# FEP_Exodia.net
KiCad netlist of a schematic drawn in EAGLE
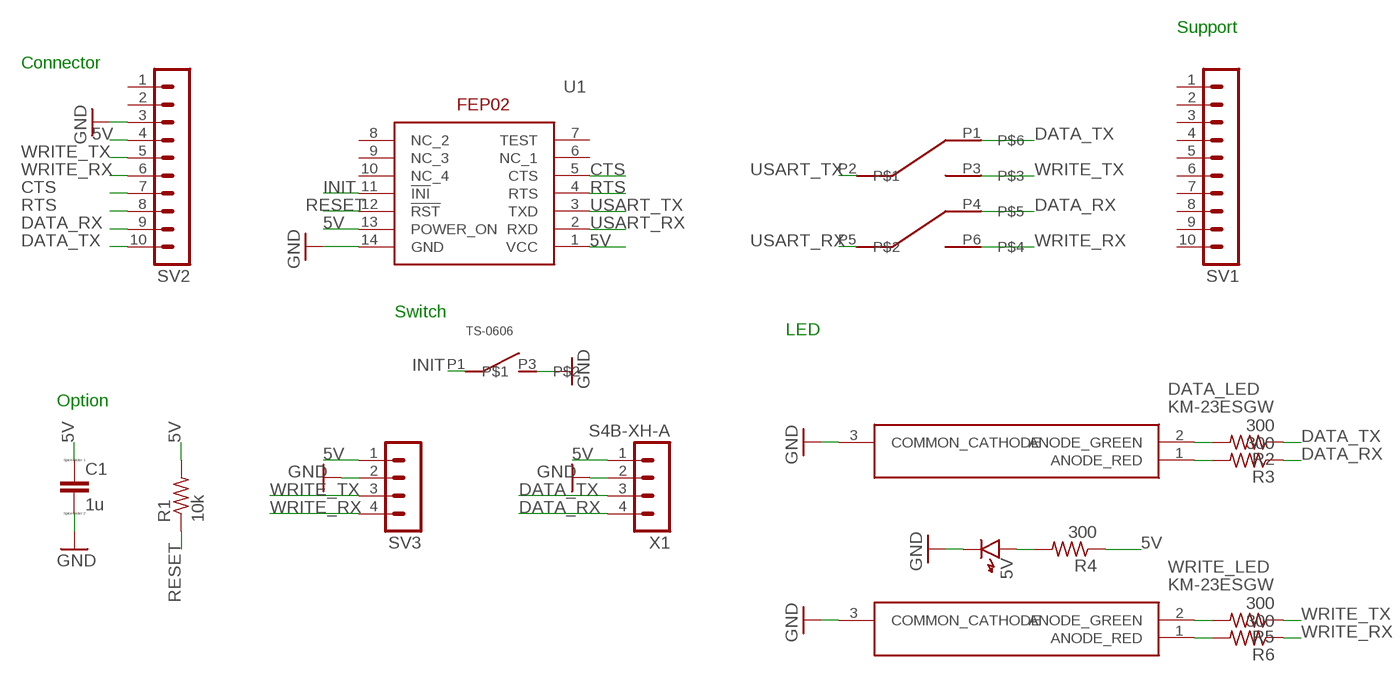
[diagram p0: schematic, sheet 1]

(export (version "E")
  (design (tool "Eeschema 10.0.6"))
  (components
    (comp (ref "5V")
      (value "LED1608")
      (footprint "eagle-import:LED1608")
      (libsource (lib "eagle-import") (part "LED1608"))
    )
    (comp (ref "C1")
      (value "1u")
      (footprint "eagle-import:C0603")
      (libsource (lib "eagle-import") (part "CC0603"))
    )
    (comp (ref "DATA_LED")
      (value "KM-23ESGW")
      (footprint "eagle-import:SOT-23")
      (libsource (lib "eagle-import") (part "KM-23ESGW"))
    )
    (comp (ref "R1")
      (value "10k")
      (footprint "eagle-import:R0603")
      (libsource (lib "eagle-import") (part "R-US_R0603"))
    )
    (comp (ref "R2")
      (value "300")
      (footprint "eagle-import:R0603")
      (libsource (lib "eagle-import") (part "R-US_R0603"))
    )
    (comp (ref "R3")
      (value "300")
      (footprint "eagle-import:R0603")
      (libsource (lib "eagle-import") (part "R-US_R0603"))
    )
    (comp (ref "R4")
      (value "300")
      (footprint "eagle-import:R0603")
      (libsource (lib "eagle-import") (part "R-US_R0603"))
    )
    (comp (ref "R5")
      (value "300")
      (footprint "eagle-import:R0603")
      (libsource (lib "eagle-import") (part "R-US_R0603"))
    )
    (comp (ref "R6")
      (value "300")
      (footprint "eagle-import:R0603")
      (libsource (lib "eagle-import") (part "R-US_R0603"))
    )
    (comp (ref "SV1")
      (value "MA10-1")
      (footprint "eagle-import:MA10-1")
      (libsource (lib "eagle-import") (part "MA10-1"))
    )
    (comp (ref "SV2")
      (value "MA10-1")
      (footprint "eagle-import:MA10-1")
      (libsource (lib "eagle-import") (part "MA10-1"))
    )
    (comp (ref "SV3")
      (value "MA04-1")
      (footprint "eagle-import:MA04-1")
      (libsource (lib "eagle-import") (part "MA04-1"))
    )
    (comp (ref "SW_1")
      (value "P-03647_TS-0606")
      (footprint "eagle-import:TS-0606")
      (libsource (lib "eagle-import") (part "P-03647_TS-0606"))
    )
    (comp (ref "SW_3")
      (value "P-08784_PS-70S")
      (footprint "eagle-import:PS-70S")
      (libsource (lib "eagle-import") (part "P-08784_PS-70S"))
    )
    (comp (ref "U1")
      (value "FEP02")
      (footprint "eagle-import:FEP02")
      (libsource (lib "eagle-import") (part "FEP02"))
    )
    (comp (ref "WRITE_LED")
      (value "KM-23ESGW")
      (footprint "eagle-import:SOT-23")
      (libsource (lib "eagle-import") (part "KM-23ESGW"))
    )
    (comp (ref "X1")
      (value "S4B-XH-A")
      (footprint "eagle-import:S4B-XH-A")
      (libsource (lib "eagle-import") (part "S4B-XH-A"))
    )
  )
  (nets
    (net (code "1") (name "/5V") (class "Default")
      (node (ref "C1") (pin "1") (pinfunction "1_1") (pintype "passive"))
      (node (ref "R1") (pin "2") (pinfunction "2_2") (pintype "passive"))
      (node (ref "R4") (pin "1") (pinfunction "1_1") (pintype "passive"))
      (node (ref "SV2") (pin "4") (pinfunction "4_4") (pintype "passive"))
      (node (ref "SV3") (pin "1") (pinfunction "1_1") (pintype "passive"))
      (node (ref "U1") (pin "1") (pinfunction "VCC_1") (pintype "bidirectional"))
      (node (ref "U1") (pin "13") (pinfunction "POWER_ON_13") (pintype "bidirectional"))
      (node (ref "X1") (pin "1") (pinfunction "1_1") (pintype "passive"))
    )
    (net (code "2") (name "/CTS") (class "Default")
      (node (ref "SV2") (pin "7") (pinfunction "7_7") (pintype "passive"))
      (node (ref "U1") (pin "5") (pinfunction "CTS_5") (pintype "bidirectional"))
    )
    (net (code "3") (name "/DATA_RX") (class "Default")
      (node (ref "R3") (pin "1") (pinfunction "1_1") (pintype "passive"))
      (node (ref "SV2") (pin "9") (pinfunction "9_9") (pintype "passive"))
      (node (ref "SW_3") (pin "P4") (pinfunction "P$5_P4") (pintype "bidirectional"))
      (node (ref "X1") (pin "4") (pinfunction "4_4") (pintype "passive"))
    )
    (net (code "4") (name "/DATA_TX") (class "Default")
      (node (ref "R2") (pin "1") (pinfunction "1_1") (pintype "passive"))
      (node (ref "SV2") (pin "10") (pinfunction "10_10") (pintype "passive"))
      (node (ref "SW_3") (pin "P1") (pinfunction "P$6_P1") (pintype "bidirectional"))
      (node (ref "X1") (pin "3") (pinfunction "3_3") (pintype "passive"))
    )
    (net (code "5") (name "/INIT") (class "Default")
      (node (ref "SW_1") (pin "P1") (pinfunction "P$1_P1") (pintype "bidirectional"))
      (node (ref "U1") (pin "11") (pinfunction "~{INI}_11") (pintype "bidirectional"))
    )
    (net (code "6") (name "/RESET") (class "Default")
      (node (ref "R1") (pin "1") (pinfunction "1_1") (pintype "passive"))
      (node (ref "U1") (pin "12") (pinfunction "~{RST}_12") (pintype "bidirectional"))
    )
    (net (code "7") (name "/RTS") (class "Default")
      (node (ref "SV2") (pin "8") (pinfunction "8_8") (pintype "passive"))
      (node (ref "U1") (pin "4") (pinfunction "RTS_4") (pintype "bidirectional"))
    )
    (net (code "8") (name "/USART_RX") (class "Default")
      (node (ref "SW_3") (pin "P5") (pinfunction "P$2_P5") (pintype "bidirectional"))
      (node (ref "U1") (pin "2") (pinfunction "RXD_2") (pintype "bidirectional"))
    )
    (net (code "9") (name "/USART_TX") (class "Default")
      (node (ref "SW_3") (pin "P2") (pinfunction "P$1_P2") (pintype "bidirectional"))
      (node (ref "U1") (pin "3") (pinfunction "TXD_3") (pintype "bidirectional"))
    )
    (net (code "10") (name "/WRITE_RX") (class "Default")
      (node (ref "R6") (pin "1") (pinfunction "1_1") (pintype "passive"))
      (node (ref "SV2") (pin "6") (pinfunction "6_6") (pintype "passive"))
      (node (ref "SV3") (pin "4") (pinfunction "4_4") (pintype "passive"))
      (node (ref "SW_3") (pin "P6") (pinfunction "P$4_P6") (pintype "bidirectional"))
    )
    (net (code "11") (name "/WRITE_TX") (class "Default")
      (node (ref "R5") (pin "1") (pinfunction "1_1") (pintype "passive"))
      (node (ref "SV2") (pin "5") (pinfunction "5_5") (pintype "passive"))
      (node (ref "SV3") (pin "3") (pinfunction "3_3") (pintype "passive"))
      (node (ref "SW_3") (pin "P3") (pinfunction "P$3_P3") (pintype "bidirectional"))
    )
    (net (code "12") (name "GND") (class "Default")
      (node (ref "5V") (pin "K") (pinfunction "K_K") (pintype "passive"))
      (node (ref "C1") (pin "2") (pinfunction "2_2") (pintype "passive"))
      (node (ref "DATA_LED") (pin "3") (pinfunction "COMMON_CATHODE_3") (pintype "bidirectional"))
      (node (ref "SV2") (pin "3") (pinfunction "3_3") (pintype "passive"))
      (node (ref "SV3") (pin "2") (pinfunction "2_2") (pintype "passive"))
      (node (ref "SW_1") (pin "P3") (pinfunction "P$2_P3") (pintype "bidirectional"))
      (node (ref "U1") (pin "14") (pinfunction "GND_14") (pintype "bidirectional"))
      (node (ref "WRITE_LED") (pin "3") (pinfunction "COMMON_CATHODE_3") (pintype "bidirectional"))
      (node (ref "X1") (pin "2") (pinfunction "2_2") (pintype "passive"))
    )
    (net (code "13") (name "Net-(5V-PadA)") (class "Default")
      (node (ref "5V") (pin "A") (pinfunction "A_A") (pintype "passive"))
      (node (ref "R4") (pin "2") (pinfunction "2_2") (pintype "passive"))
    )
    (net (code "14") (name "Net-(DATA_LED-ANODE_GREEN)") (class "Default")
      (node (ref "DATA_LED") (pin "2") (pinfunction "ANODE_GREEN_2") (pintype "bidirectional"))
      (node (ref "R2") (pin "2") (pinfunction "2_2") (pintype "passive"))
    )
    (net (code "15") (name "Net-(DATA_LED-ANODE_RED)") (class "Default")
      (node (ref "DATA_LED") (pin "1") (pinfunction "ANODE_RED_1") (pintype "bidirectional"))
      (node (ref "R3") (pin "2") (pinfunction "2_2") (pintype "passive"))
    )
    (net (code "16") (name "Net-(WRITE_LED-ANODE_GREEN)") (class "Default")
      (node (ref "R5") (pin "2") (pinfunction "2_2") (pintype "passive"))
      (node (ref "WRITE_LED") (pin "2") (pinfunction "ANODE_GREEN_2") (pintype "bidirectional"))
    )
    (net (code "17") (name "Net-(WRITE_LED-ANODE_RED)") (class "Default")
      (node (ref "R6") (pin "2") (pinfunction "2_2") (pintype "passive"))
      (node (ref "WRITE_LED") (pin "1") (pinfunction "ANODE_RED_1") (pintype "bidirectional"))
    )
    (net (code "18") (name "unconnected-(SV1-Pad1)") (class "Default")
      (node (ref "SV1") (pin "1") (pinfunction "1_1") (pintype "passive"))
    )
    (net (code "19") (name "unconnected-(SV1-Pad2)") (class "Default")
      (node (ref "SV1") (pin "2") (pinfunction "2_2") (pintype "passive"))
    )
    (net (code "20") (name "unconnected-(SV1-Pad3)") (class "Default")
      (node (ref "SV1") (pin "3") (pinfunction "3_3") (pintype "passive"))
    )
    (net (code "21") (name "unconnected-(SV1-Pad4)") (class "Default")
      (node (ref "SV1") (pin "4") (pinfunction "4_4") (pintype "passive"))
    )
    (net (code "22") (name "unconnected-(SV1-Pad5)") (class "Default")
      (node (ref "SV1") (pin "5") (pinfunction "5_5") (pintype "passive"))
    )
    (net (code "23") (name "unconnected-(SV1-Pad6)") (class "Default")
      (node (ref "SV1") (pin "6") (pinfunction "6_6") (pintype "passive"))
    )
    (net (code "24") (name "unconnected-(SV1-Pad7)") (class "Default")
      (node (ref "SV1") (pin "7") (pinfunction "7_7") (pintype "passive"))
    )
    (net (code "25") (name "unconnected-(SV1-Pad8)") (class "Default")
      (node (ref "SV1") (pin "8") (pinfunction "8_8") (pintype "passive"))
    )
    (net (code "26") (name "unconnected-(SV1-Pad9)") (class "Default")
      (node (ref "SV1") (pin "9") (pinfunction "9_9") (pintype "passive"))
    )
    (net (code "27") (name "unconnected-(SV1-Pad10)") (class "Default")
      (node (ref "SV1") (pin "10") (pinfunction "10_10") (pintype "passive"))
    )
    (net (code "28") (name "unconnected-(SV2-Pad1)") (class "Default")
      (node (ref "SV2") (pin "1") (pinfunction "1_1") (pintype "passive"))
    )
    (net (code "29") (name "unconnected-(SV2-Pad2)") (class "Default")
      (node (ref "SV2") (pin "2") (pinfunction "2_2") (pintype "passive"))
    )
    (net (code "30") (name "unconnected-(U1-NC_1-Pad6)") (class "Default")
      (node (ref "U1") (pin "6") (pinfunction "NC_1_6") (pintype "bidirectional"))
    )
    (net (code "31") (name "unconnected-(U1-NC_2-Pad8)") (class "Default")
      (node (ref "U1") (pin "8") (pinfunction "NC_2_8") (pintype "bidirectional"))
    )
    (net (code "32") (name "unconnected-(U1-NC_3-Pad9)") (class "Default")
      (node (ref "U1") (pin "9") (pinfunction "NC_3_9") (pintype "bidirectional"))
    )
    (net (code "33") (name "unconnected-(U1-NC_4-Pad10)") (class "Default")
      (node (ref "U1") (pin "10") (pinfunction "NC_4_10") (pintype "bidirectional"))
    )
    (net (code "34") (name "unconnected-(U1-TEST-Pad7)") (class "Default")
      (node (ref "U1") (pin "7") (pinfunction "TEST_7") (pintype "bidirectional"))
    )
  )
)
